# EVB-NORA-B2_SCHEM_0002_NORA_Module.net
KiCad netlist of a schematic drawn in Altium Designer
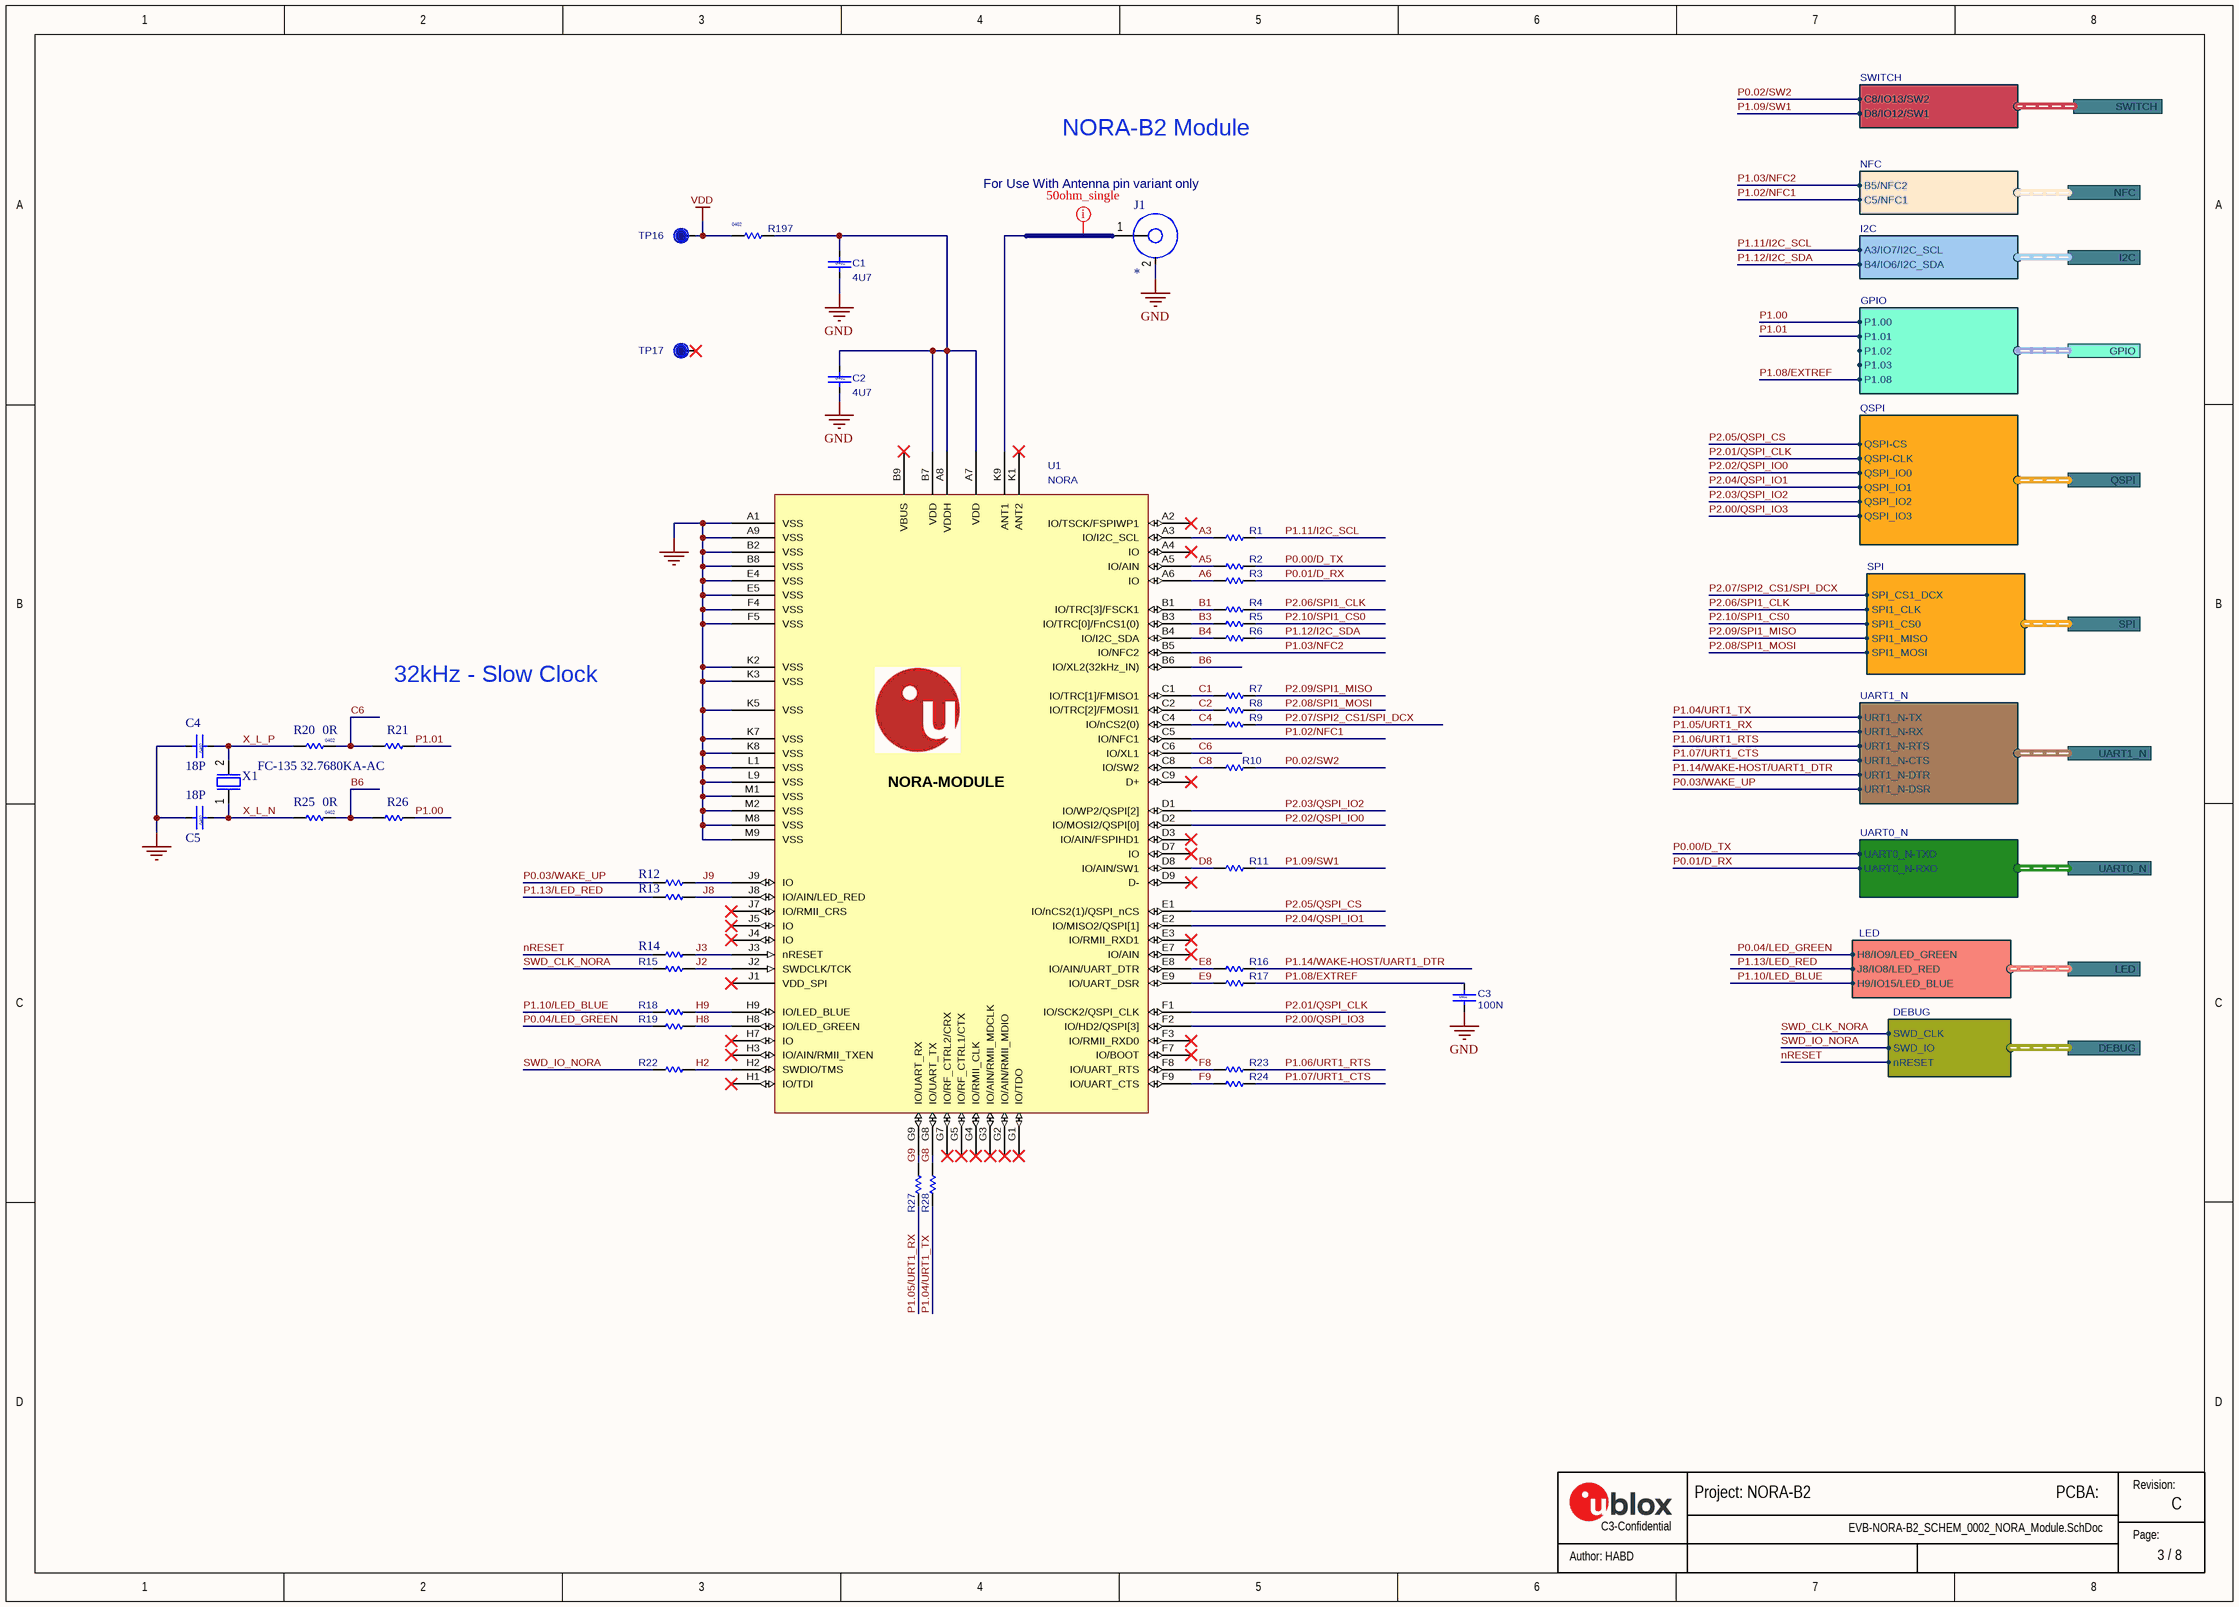
[diagram p0: EVB-NORA-B2_SCHEM_0002_NORA_Module.SchDoc]

(export (version "E")
  (design (tool "Eeschema 10.0.6"))
  (components
    (comp (ref "C1")
      (value "4U7")
      (footprint "Cap 0402 HD")
      (description "CAP CER X5R 0402 4U7 20% 10V")
      (fields
        (field (name "SIZE") "0402")
        (field (name "PART NUMBER") "UBXH01-0000243")
        (field (name "TOLERANCE") "20%")
        (field (name "EDITOR") "martin.pilik")
        (field (name "RELEASED BY") "fabrice.bret-dibat")
      )
      (libsource (lib "UBX_Parts_DB_Lib") (part "Cap Chip"))
    )
    (comp (ref "C2")
      (value "4U7")
      (footprint "Cap 0402 HD")
      (description "CAP CER X5R 0402 4U7 20% 10V")
      (fields
        (field (name "SIZE") "0402")
        (field (name "PART NUMBER") "UBXH01-0000243")
        (field (name "TOLERANCE") "20%")
        (field (name "EDITOR") "martin.pilik")
        (field (name "RELEASED BY") "fabrice.bret-dibat")
      )
      (libsource (lib "UBX_Parts_DB_Lib") (part "Cap Chip"))
    )
    (comp (ref "C3")
      (value "100N")
      (footprint "Cap 0402 HD")
      (description "CAP CER X5R 0402 100N 10% 10V")
      (fields
        (field (name "SIZE") "0402")
        (field (name "PART NUMBER") "UBXH01-2021002")
        (field (name "TOLERANCE") "10%")
        (field (name "EDITOR") "roland.rust")
        (field (name "RELEASED BY") "roland.rust")
      )
      (libsource (lib "UBX_Parts_DB_Lib") (part "Cap Chip"))
    )
    (comp (ref "C4")
      (value "18P")
      (footprint "Cap_0402_1100Lx600Wx600H_600x600Pad_350G_FLX")
      (description "CAP CER C0G 0402 18P 5% 25V")
      (fields
        (field (name "SIZE") "0402")
        (field (name "PART NUMBER") "UBXH01-0004017")
        (field (name "TOLERANCE") "5%")
        (field (name "EDITOR") "doris.zahnd")
        (field (name "RELEASED BY") "daniel.hurni")
      )
      (libsource (lib "UBX_Parts_DB_Lib") (part "Cap Chip"))
    )
    (comp (ref "C5")
      (value "18P")
      (footprint "Cap_0402_1100Lx600Wx600H_600x600Pad_350G_FLX")
      (description "CAP CER C0G 0402 18P 5% 25V")
      (fields
        (field (name "SIZE") "0402")
        (field (name "PART NUMBER") "UBXH01-0004017")
        (field (name "TOLERANCE") "5%")
        (field (name "EDITOR") "doris.zahnd")
        (field (name "RELEASED BY") "daniel.hurni")
      )
      (libsource (lib "UBX_Parts_DB_Lib") (part "Cap Chip"))
    )
    (comp (ref "J1")
      (value "130-00067")
      (footprint "U.FL_3Pin")
      (description "U.FL jack, SMA 50 ohm, 3 pin, SMT")
      (fields (field (name "MANUFACTURER P/N") "*") (field (name "VOLTAGE") "None"))
      (libsource (lib "Arena_Parts_DB_Lib") (part "CON_Coax_2Pin"))
    )
    (comp (ref "R1")
      (value "UBXH18-0003002")
      (footprint "RES 0402 HD")
      (description "RES THICK FILM CHIP 0402 0R 0 100mW")
      (fields
        (field (name "TOLERANCE") "0")
        (field (name "MANUFACTURER") "KOA")
        (field (name "EDITOR") "charlotte.biber")
        (field (name "RELEASED BY") "peter.mueller")
      )
      (libsource (lib "UBX_Parts_DB_Lib") (part "Res sm"))
    )
    (comp (ref "R2")
      (value "UBXH18-0003002")
      (footprint "RES 0402 HD")
      (description "RES THICK FILM CHIP 0402 0R 0 100mW")
      (fields
        (field (name "TOLERANCE") "0")
        (field (name "MANUFACTURER") "KOA")
        (field (name "EDITOR") "charlotte.biber")
        (field (name "RELEASED BY") "peter.mueller")
      )
      (libsource (lib "UBX_Parts_DB_Lib") (part "Res sm"))
    )
    (comp (ref "R3")
      (value "UBXH18-0003002")
      (footprint "RES 0402 HD")
      (description "RES THICK FILM CHIP 0402 0R 0 100mW")
      (fields
        (field (name "TOLERANCE") "0")
        (field (name "MANUFACTURER") "KOA")
        (field (name "EDITOR") "charlotte.biber")
        (field (name "RELEASED BY") "peter.mueller")
      )
      (libsource (lib "UBX_Parts_DB_Lib") (part "Res sm"))
    )
    (comp (ref "R4")
      (value "UBXH18-0003002")
      (footprint "RES 0402 HD")
      (description "RES THICK FILM CHIP 0402 0R 0 100mW")
      (fields
        (field (name "TOLERANCE") "0")
        (field (name "MANUFACTURER") "KOA")
        (field (name "EDITOR") "charlotte.biber")
        (field (name "RELEASED BY") "peter.mueller")
      )
      (libsource (lib "UBX_Parts_DB_Lib") (part "Res sm"))
    )
    (comp (ref "R5")
      (value "UBXH18-0003002")
      (footprint "RES 0402 HD")
      (description "RES THICK FILM CHIP 0402 0R 0 100mW")
      (fields
        (field (name "TOLERANCE") "0")
        (field (name "MANUFACTURER") "KOA")
        (field (name "EDITOR") "charlotte.biber")
        (field (name "RELEASED BY") "peter.mueller")
      )
      (libsource (lib "UBX_Parts_DB_Lib") (part "Res sm"))
    )
    (comp (ref "R6")
      (value "UBXH18-0003002")
      (footprint "RES 0402 HD")
      (description "RES THICK FILM CHIP 0402 0R 0 100mW")
      (fields
        (field (name "TOLERANCE") "0")
        (field (name "MANUFACTURER") "KOA")
        (field (name "EDITOR") "charlotte.biber")
        (field (name "RELEASED BY") "peter.mueller")
      )
      (libsource (lib "UBX_Parts_DB_Lib") (part "Res sm"))
    )
    (comp (ref "R7")
      (value "UBXH18-0003002")
      (footprint "RES 0402 HD")
      (description "RES THICK FILM CHIP 0402 0R 0 100mW")
      (fields
        (field (name "TOLERANCE") "0")
        (field (name "MANUFACTURER") "KOA")
        (field (name "EDITOR") "charlotte.biber")
        (field (name "RELEASED BY") "peter.mueller")
      )
      (libsource (lib "UBX_Parts_DB_Lib") (part "Res sm"))
    )
    (comp (ref "R8")
      (value "UBXH18-0003002")
      (footprint "RES 0402 HD")
      (description "RES THICK FILM CHIP 0402 0R 0 100mW")
      (fields
        (field (name "TOLERANCE") "0")
        (field (name "MANUFACTURER") "KOA")
        (field (name "EDITOR") "charlotte.biber")
        (field (name "RELEASED BY") "peter.mueller")
      )
      (libsource (lib "UBX_Parts_DB_Lib") (part "Res sm"))
    )
    (comp (ref "R9")
      (value "UBXH18-0003002")
      (footprint "RES 0402 HD")
      (description "RES THICK FILM CHIP 0402 0R 0 100mW")
      (fields
        (field (name "TOLERANCE") "0")
        (field (name "MANUFACTURER") "KOA")
        (field (name "EDITOR") "charlotte.biber")
        (field (name "RELEASED BY") "peter.mueller")
      )
      (libsource (lib "UBX_Parts_DB_Lib") (part "Res sm"))
    )
    (comp (ref "R10")
      (value "UBXH18-0003002")
      (footprint "RES 0402 HD")
      (description "RES THICK FILM CHIP 0402 0R 0 100mW")
      (fields
        (field (name "TOLERANCE") "0")
        (field (name "MANUFACTURER") "KOA")
        (field (name "EDITOR") "charlotte.biber")
        (field (name "RELEASED BY") "peter.mueller")
      )
      (libsource (lib "UBX_Parts_DB_Lib") (part "Res sm"))
    )
    (comp (ref "R11")
      (value "UBXH18-0003002")
      (footprint "RES 0402 HD")
      (description "RES THICK FILM CHIP 0402 0R 0 100mW")
      (fields
        (field (name "TOLERANCE") "0")
        (field (name "MANUFACTURER") "KOA")
        (field (name "EDITOR") "charlotte.biber")
        (field (name "RELEASED BY") "peter.mueller")
      )
      (libsource (lib "UBX_Parts_DB_Lib") (part "Res sm"))
    )
    (comp (ref "R12")
      (value "UBXH18-0003002")
      (footprint "RES_0402_1100Lx600Wx400H_500x600Pad_400G_FLX")
      (description "RES THICK FILM CHIP 0402 0R 0 100mW")
      (fields
        (field (name "TOLERANCE") "0")
        (field (name "MANUFACTURER") "KOA")
        (field (name "EDITOR") "charlotte.biber")
        (field (name "RELEASED BY") "peter.mueller")
      )
      (libsource (lib "UBX_Parts_DB_Lib") (part "Res sm"))
    )
    (comp (ref "R13")
      (value "UBXH18-0003002")
      (footprint "RES_0402_1100Lx600Wx400H_500x600Pad_400G_FLX")
      (description "RES THICK FILM CHIP 0402 0R 0 100mW")
      (fields
        (field (name "TOLERANCE") "0")
        (field (name "MANUFACTURER") "KOA")
        (field (name "EDITOR") "charlotte.biber")
        (field (name "RELEASED BY") "peter.mueller")
      )
      (libsource (lib "UBX_Parts_DB_Lib") (part "Res sm"))
    )
    (comp (ref "R14")
      (value "UBXH18-0003002")
      (footprint "RES_0402_1100Lx600Wx400H_500x600Pad_400G_FLX")
      (description "RES THICK FILM CHIP 0402 0R 0 100mW")
      (fields
        (field (name "TOLERANCE") "0")
        (field (name "MANUFACTURER") "KOA")
        (field (name "EDITOR") "charlotte.biber")
        (field (name "RELEASED BY") "peter.mueller")
      )
      (libsource (lib "UBX_Parts_DB_Lib") (part "Res sm"))
    )
    (comp (ref "R15")
      (value "UBXH18-0003002")
      (footprint "RES 0402 HD")
      (description "RES THICK FILM CHIP 0402 0R 0 100mW")
      (fields
        (field (name "TOLERANCE") "0")
        (field (name "MANUFACTURER") "KOA")
        (field (name "EDITOR") "charlotte.biber")
        (field (name "RELEASED BY") "peter.mueller")
      )
      (libsource (lib "UBX_Parts_DB_Lib") (part "Res sm"))
    )
    (comp (ref "R16")
      (value "UBXH18-0003002")
      (footprint "RES 0402 HD")
      (description "RES THICK FILM CHIP 0402 0R 0 100mW")
      (fields
        (field (name "TOLERANCE") "0")
        (field (name "MANUFACTURER") "KOA")
        (field (name "EDITOR") "charlotte.biber")
        (field (name "RELEASED BY") "peter.mueller")
      )
      (libsource (lib "UBX_Parts_DB_Lib") (part "Res sm"))
    )
    (comp (ref "R17")
      (value "UBXH18-0003002")
      (footprint "RES 0402 HD")
      (description "RES THICK FILM CHIP 0402 0R 0 100mW")
      (fields
        (field (name "TOLERANCE") "0")
        (field (name "MANUFACTURER") "KOA")
        (field (name "EDITOR") "charlotte.biber")
        (field (name "RELEASED BY") "peter.mueller")
      )
      (libsource (lib "UBX_Parts_DB_Lib") (part "Res sm"))
    )
    (comp (ref "R18")
      (value "UBXH18-0003002")
      (footprint "RES 0402 HD")
      (description "RES THICK FILM CHIP 0402 0R 0 100mW")
      (fields
        (field (name "TOLERANCE") "0")
        (field (name "MANUFACTURER") "KOA")
        (field (name "EDITOR") "charlotte.biber")
        (field (name "RELEASED BY") "peter.mueller")
      )
      (libsource (lib "UBX_Parts_DB_Lib") (part "Res sm"))
    )
    (comp (ref "R19")
      (value "UBXH18-0003002")
      (footprint "RES 0402 HD")
      (description "RES THICK FILM CHIP 0402 0R 0 100mW")
      (fields
        (field (name "TOLERANCE") "0")
        (field (name "MANUFACTURER") "KOA")
        (field (name "EDITOR") "charlotte.biber")
        (field (name "RELEASED BY") "peter.mueller")
      )
      (libsource (lib "UBX_Parts_DB_Lib") (part "Res sm"))
    )
    (comp (ref "R20")
      (value "0R")
      (footprint "RES 0402 HD")
      (description "RES THICK FILM CHIP 0402 0R 0 100mW")
      (fields
        (field (name "SIZE") "0402")
        (field (name "PART NUMBER") "UBXH18-0003002")
        (field (name "TOLERANCE") "0")
        (field (name "EDITOR") "charlotte.biber")
        (field (name "RELEASED BY") "peter.mueller")
      )
      (libsource (lib "UBX_Parts_DB_Lib") (part "Res sm"))
    )
    (comp (ref "R21")
      (value "UBXH18-0003002")
      (footprint "RES_0402_1100Lx600Wx400H_500x600Pad_400G_FLX")
      (description "RES THICK FILM CHIP 0402 0R 0 100mW")
      (fields
        (field (name "TOLERANCE") "0")
        (field (name "MANUFACTURER") "KOA")
        (field (name "EDITOR") "charlotte.biber")
        (field (name "RELEASED BY") "peter.mueller")
      )
      (libsource (lib "UBX_Parts_DB_Lib") (part "Res sm"))
    )
    (comp (ref "R22")
      (value "UBXH18-0003002")
      (footprint "RES 0402 HD")
      (description "RES THICK FILM CHIP 0402 0R 0 100mW")
      (fields
        (field (name "TOLERANCE") "0")
        (field (name "MANUFACTURER") "KOA")
        (field (name "EDITOR") "charlotte.biber")
        (field (name "RELEASED BY") "peter.mueller")
      )
      (libsource (lib "UBX_Parts_DB_Lib") (part "Res sm"))
    )
    (comp (ref "R23")
      (value "UBXH18-0003002")
      (footprint "RES 0402 HD")
      (description "RES THICK FILM CHIP 0402 0R 0 100mW")
      (fields
        (field (name "TOLERANCE") "0")
        (field (name "MANUFACTURER") "KOA")
        (field (name "EDITOR") "charlotte.biber")
        (field (name "RELEASED BY") "peter.mueller")
      )
      (libsource (lib "UBX_Parts_DB_Lib") (part "Res sm"))
    )
    (comp (ref "R24")
      (value "UBXH18-0003002")
      (footprint "RES 0402 HD")
      (description "RES THICK FILM CHIP 0402 0R 0 100mW")
      (fields
        (field (name "TOLERANCE") "0")
        (field (name "MANUFACTURER") "KOA")
        (field (name "EDITOR") "charlotte.biber")
        (field (name "RELEASED BY") "peter.mueller")
      )
      (libsource (lib "UBX_Parts_DB_Lib") (part "Res sm"))
    )
    (comp (ref "R25")
      (value "0R")
      (footprint "RES 0402 HD")
      (description "RES THICK FILM CHIP 0402 0R 0 100mW")
      (fields
        (field (name "SIZE") "0402")
        (field (name "PART NUMBER") "UBXH18-0003002")
        (field (name "TOLERANCE") "0")
        (field (name "EDITOR") "charlotte.biber")
        (field (name "RELEASED BY") "peter.mueller")
      )
      (libsource (lib "UBX_Parts_DB_Lib") (part "Res sm"))
    )
    (comp (ref "R26")
      (value "UBXH18-0003002")
      (footprint "RES_0402_1100Lx600Wx400H_500x600Pad_400G_FLX")
      (description "RES THICK FILM CHIP 0402 0R 0 100mW")
      (fields
        (field (name "TOLERANCE") "0")
        (field (name "MANUFACTURER") "KOA")
        (field (name "EDITOR") "charlotte.biber")
        (field (name "RELEASED BY") "peter.mueller")
      )
      (libsource (lib "UBX_Parts_DB_Lib") (part "Res sm"))
    )
    (comp (ref "R27")
      (value "UBXH18-0003002")
      (footprint "RES 0402 HD")
      (description "RES THICK FILM CHIP 0402 0R 0 100mW")
      (fields
        (field (name "TOLERANCE") "0")
        (field (name "MANUFACTURER") "KOA")
        (field (name "EDITOR") "charlotte.biber")
        (field (name "RELEASED BY") "peter.mueller")
      )
      (libsource (lib "UBX_Parts_DB_Lib") (part "Res sm"))
    )
    (comp (ref "R28")
      (value "UBXH18-0003002")
      (footprint "RES 0402 HD")
      (description "RES THICK FILM CHIP 0402 0R 0 100mW")
      (fields
        (field (name "TOLERANCE") "0")
        (field (name "MANUFACTURER") "KOA")
        (field (name "EDITOR") "charlotte.biber")
        (field (name "RELEASED BY") "peter.mueller")
      )
      (libsource (lib "UBX_Parts_DB_Lib") (part "Res sm"))
    )
    (comp (ref "R197")
      (value "UBXH18-0003002")
      (footprint "RES 0402 HD")
      (description "RES THICK FILM CHIP 0402 0R 0 100mW")
      (fields
        (field (name "SIZE") "0402")
        (field (name "TOLERANCE") "0")
        (field (name "MANUFACTURER") "KOA")
        (field (name "EDITOR") "charlotte.biber")
        (field (name "RELEASED BY") "peter.mueller")
      )
      (libsource (lib "UBX_Parts_DB_Lib") (part "Res sm"))
    )
    (comp (ref "TP16")
      (value "TP10R")
      (footprint "TP10R")
      (description "Testpoint, Round 1.0mm Dia")
      (fields (field (name "ADDED BY") "Jeremy D") (field (name "CHECKED BY") "Paul B"))
      (libsource (lib "LEGACY_Rigado_AltiumLib") (part "TP_R"))
    )
    (comp (ref "TP17")
      (value "TP10R")
      (footprint "TP10R")
      (description "Testpoint, Round 1.0mm Dia")
      (fields (field (name "ADDED BY") "Jeremy D") (field (name "CHECKED BY") "Paul B"))
      (libsource (lib "LEGACY_Rigado_AltiumLib") (part "TP_R"))
    )
    (comp (ref "U1")
      (value "NORA")
      (footprint "NORA:NORA_LGA82R_1430X1040X180_ANT")
      (description "u-blox NORA module generic symbol for use within module designs - alternate version")
      (fields (field (name "MANUFACTURER") "u-blox"))
      (libsource (lib "NORA") (part "NORA-MODULE_ALT"))
    )
    (comp (ref "X1")
      (value "UBXH21-0008104")
      (footprint "XTAL_3215")
      (description "CRYSTAL CL=9PF EPSON FC-135 NI/SN TERMINATION 32.768KHz")
      (fields (field (name "MANUFACTURER P/N") "FC-135 32.7680KA-AC") (field (name "OWNER") "Andreas Thiel"))
      (libsource (lib "UBX_Arena") (part "XTAL_2Pin"))
    )
  )
  (nets
    (net (code "11") (name "/A3") (class "Default")
      (node (ref "R1") (pin "2") (pinfunction "2_2") (pintype "passive"))
      (node (ref "U1") (pin "A3") (pinfunction "IO/I2C_SCL_A3") (pintype "bidirectional"))
    )
    (net (code "12") (name "/A5") (class "Default")
      (node (ref "R2") (pin "2") (pinfunction "2_2") (pintype "passive"))
      (node (ref "U1") (pin "A5") (pinfunction "IO/AIN_A5") (pintype "bidirectional"))
    )
    (net (code "13") (name "/A6") (class "Default")
      (node (ref "R3") (pin "2") (pinfunction "2_2") (pintype "passive"))
      (node (ref "U1") (pin "A6") (pinfunction "IO_A6") (pintype "bidirectional"))
    )
    (net (code "14") (name "/B1") (class "Default")
      (node (ref "R4") (pin "2") (pinfunction "2_2") (pintype "passive"))
      (node (ref "U1") (pin "B1") (pinfunction "IO/TRC[3]/FSCK1_B1") (pintype "bidirectional"))
    )
    (net (code "15") (name "/B3") (class "Default")
      (node (ref "R5") (pin "2") (pinfunction "2_2") (pintype "passive"))
      (node (ref "U1") (pin "B3") (pinfunction "IO/TRC[0]/FnCS1(0)_B3") (pintype "bidirectional"))
    )
    (net (code "16") (name "/B4") (class "Default")
      (node (ref "R6") (pin "2") (pinfunction "2_2") (pintype "passive"))
      (node (ref "U1") (pin "B4") (pinfunction "IO/I2C_SDA_B4") (pintype "bidirectional"))
    )
    (net (code "17") (name "/B6") (class "Default")
      (node (ref "R25") (pin "2") (pinfunction "2_2") (pintype "passive"))
      (node (ref "R26") (pin "2") (pinfunction "2_2") (pintype "passive"))
      (node (ref "U1") (pin "B6") (pinfunction "IO/XL2(32kHz_IN)_B6") (pintype "bidirectional"))
    )
    (net (code "18") (name "/C1") (class "Default")
      (node (ref "R7") (pin "2") (pinfunction "2_2") (pintype "passive"))
      (node (ref "U1") (pin "C1") (pinfunction "IO/TRC[1]/FMISO1_C1") (pintype "bidirectional"))
    )
    (net (code "19") (name "/C2") (class "Default")
      (node (ref "R8") (pin "2") (pinfunction "2_2") (pintype "passive"))
      (node (ref "U1") (pin "C2") (pinfunction "IO/TRC[2]/FMOSI1_C2") (pintype "bidirectional"))
    )
    (net (code "20") (name "/C4") (class "Default")
      (node (ref "R9") (pin "2") (pinfunction "2_2") (pintype "passive"))
      (node (ref "U1") (pin "C4") (pinfunction "IO/nCS2(0)_C4") (pintype "bidirectional"))
    )
    (net (code "21") (name "/C6") (class "Default")
      (node (ref "R20") (pin "2") (pinfunction "2_2") (pintype "passive"))
      (node (ref "R21") (pin "2") (pinfunction "2_2") (pintype "passive"))
      (node (ref "U1") (pin "C6") (pinfunction "IO/XL1_C6") (pintype "bidirectional"))
    )
    (net (code "22") (name "/C8") (class "Default")
      (node (ref "R10") (pin "2") (pinfunction "2_2") (pintype "passive"))
      (node (ref "U1") (pin "C8") (pinfunction "IO/SW2_C8") (pintype "bidirectional"))
    )
    (net (code "23") (name "/D8") (class "Default")
      (node (ref "R11") (pin "2") (pinfunction "2_2") (pintype "passive"))
      (node (ref "U1") (pin "D8") (pinfunction "IO/AIN/SW1_D8") (pintype "bidirectional"))
    )
    (net (code "24") (name "/E8") (class "Default")
      (node (ref "R16") (pin "2") (pinfunction "2_2") (pintype "passive"))
      (node (ref "U1") (pin "E8") (pinfunction "IO/AIN/UART_DTR_E8") (pintype "bidirectional"))
    )
    (net (code "25") (name "/E9") (class "Default")
      (node (ref "R17") (pin "2") (pinfunction "2_2") (pintype "passive"))
      (node (ref "U1") (pin "E9") (pinfunction "IO/UART_DSR_E9") (pintype "bidirectional"))
    )
    (net (code "26") (name "/F8") (class "Default")
      (node (ref "R23") (pin "2") (pinfunction "2_2") (pintype "passive"))
      (node (ref "U1") (pin "F8") (pinfunction "IO/UART_RTS_F8") (pintype "bidirectional"))
    )
    (net (code "27") (name "/F9") (class "Default")
      (node (ref "R24") (pin "2") (pinfunction "2_2") (pintype "passive"))
      (node (ref "U1") (pin "F9") (pinfunction "IO/UART_CTS_F9") (pintype "bidirectional"))
    )
    (net (code "28") (name "/G8") (class "Default")
      (node (ref "R28") (pin "1") (pinfunction "1_1") (pintype "passive"))
      (node (ref "U1") (pin "G8") (pinfunction "IO/UART_TX_G8") (pintype "bidirectional"))
    )
    (net (code "29") (name "/G9") (class "Default")
      (node (ref "R27") (pin "1") (pinfunction "1_1") (pintype "passive"))
      (node (ref "U1") (pin "G9") (pinfunction "IO/UART_RX_G9") (pintype "bidirectional"))
    )
    (net (code "30") (name "/H2") (class "Default")
      (node (ref "R22") (pin "1") (pinfunction "1_1") (pintype "passive"))
      (node (ref "U1") (pin "H2") (pinfunction "SWDIO/TMS_H2") (pintype "bidirectional"))
    )
    (net (code "31") (name "/H8") (class "Default")
      (node (ref "R19") (pin "1") (pinfunction "1_1") (pintype "passive"))
      (node (ref "U1") (pin "H8") (pinfunction "IO/LED_GREEN_H8") (pintype "bidirectional"))
    )
    (net (code "32") (name "/H9") (class "Default")
      (node (ref "R18") (pin "1") (pinfunction "1_1") (pintype "passive"))
      (node (ref "U1") (pin "H9") (pinfunction "IO/LED_BLUE_H9") (pintype "bidirectional"))
    )
    (net (code "33") (name "/J2") (class "Default")
      (node (ref "R15") (pin "1") (pinfunction "1_1") (pintype "passive"))
      (node (ref "U1") (pin "J2") (pinfunction "SWDCLK/TCK_J2") (pintype "input"))
    )
    (net (code "34") (name "/J3") (class "Default")
      (node (ref "R14") (pin "1") (pinfunction "1_1") (pintype "passive"))
      (node (ref "U1") (pin "J3") (pinfunction "nRESET_J3") (pintype "input"))
    )
    (net (code "35") (name "/J8") (class "Default")
      (node (ref "R13") (pin "1") (pinfunction "1_1") (pintype "passive"))
      (node (ref "U1") (pin "J8") (pinfunction "IO/AIN/LED_RED_J8") (pintype "bidirectional"))
    )
    (net (code "36") (name "/J9") (class "Default")
      (node (ref "R12") (pin "1") (pinfunction "1_1") (pintype "passive"))
      (node (ref "U1") (pin "J9") (pinfunction "IO_J9") (pintype "bidirectional"))
    )
    (net (code "37") (name "/P0.00{slash}D_TX") (class "Default")
      (node (ref "R2") (pin "1") (pinfunction "1_1") (pintype "passive"))
    )
    (net (code "38") (name "/P0.01{slash}D_RX") (class "Default")
      (node (ref "R3") (pin "1") (pinfunction "1_1") (pintype "passive"))
    )
    (net (code "39") (name "/P0.02{slash}SW2") (class "Default")
      (node (ref "R10") (pin "1") (pinfunction "1_1") (pintype "passive"))
    )
    (net (code "40") (name "/P0.03{slash}WAKE_UP") (class "Default")
      (node (ref "R12") (pin "2") (pinfunction "2_2") (pintype "passive"))
    )
    (net (code "41") (name "/P0.04{slash}LED_GREEN") (class "Default")
      (node (ref "R19") (pin "2") (pinfunction "2_2") (pintype "passive"))
    )
    (net (code "42") (name "/P1.00") (class "Default")
      (node (ref "R26") (pin "1") (pinfunction "1_1") (pintype "passive"))
    )
    (net (code "43") (name "/P1.01") (class "Default")
      (node (ref "R21") (pin "1") (pinfunction "1_1") (pintype "passive"))
    )
    (net (code "44") (name "/P1.02{slash}NFC1") (class "Default")
      (node (ref "U1") (pin "C5") (pinfunction "IO/NFC1_C5") (pintype "bidirectional"))
    )
    (net (code "45") (name "/P1.03{slash}NFC2") (class "Default")
      (node (ref "U1") (pin "B5") (pinfunction "IO/NFC2_B5") (pintype "bidirectional"))
    )
    (net (code "46") (name "/P1.04{slash}URT1_TX") (class "Default")
      (node (ref "R28") (pin "2") (pinfunction "2_2") (pintype "passive"))
    )
    (net (code "47") (name "/P1.05{slash}URT1_RX") (class "Default")
      (node (ref "R27") (pin "2") (pinfunction "2_2") (pintype "passive"))
    )
    (net (code "48") (name "/P1.06{slash}URT1_RTS") (class "Default")
      (node (ref "R23") (pin "1") (pinfunction "1_1") (pintype "passive"))
    )
    (net (code "49") (name "/P1.07{slash}URT1_CTS") (class "Default")
      (node (ref "R24") (pin "1") (pinfunction "1_1") (pintype "passive"))
    )
    (net (code "50") (name "/P1.08{slash}EXTREF") (class "Default")
      (node (ref "C3") (pin "2") (pinfunction "2_2") (pintype "passive"))
      (node (ref "R17") (pin "1") (pinfunction "1_1") (pintype "passive"))
    )
    (net (code "51") (name "/P1.09{slash}SW1") (class "Default")
      (node (ref "R11") (pin "1") (pinfunction "1_1") (pintype "passive"))
    )
    (net (code "52") (name "/P1.10{slash}LED_BLUE") (class "Default")
      (node (ref "R18") (pin "2") (pinfunction "2_2") (pintype "passive"))
    )
    (net (code "53") (name "/P1.11{slash}I2C_SCL") (class "Default")
      (node (ref "R1") (pin "1") (pinfunction "1_1") (pintype "passive"))
    )
    (net (code "54") (name "/P1.12{slash}I2C_SDA") (class "Default")
      (node (ref "R6") (pin "1") (pinfunction "1_1") (pintype "passive"))
    )
    (net (code "55") (name "/P1.13{slash}LED_RED") (class "Default")
      (node (ref "R13") (pin "2") (pinfunction "2_2") (pintype "passive"))
    )
    (net (code "56") (name "/P1.14{slash}WAKE-HOST{slash}UART1_DTR") (class "Default")
      (node (ref "R16") (pin "1") (pinfunction "1_1") (pintype "passive"))
    )
    (net (code "57") (name "/P2.00{slash}QSPI_IO3") (class "Default")
      (node (ref "U1") (pin "F2") (pinfunction "IO/HD2/QSPI[3]_F2") (pintype "bidirectional"))
    )
    (net (code "58") (name "/P2.01{slash}QSPI_CLK") (class "Default")
      (node (ref "U1") (pin "F1") (pinfunction "IO/SCK2/QSPI_CLK_F1") (pintype "bidirectional"))
    )
    (net (code "59") (name "/P2.02{slash}QSPI_IO0") (class "Default")
      (node (ref "U1") (pin "D2") (pinfunction "IO/MOSI2/QSPI[0]_D2") (pintype "bidirectional"))
    )
    (net (code "60") (name "/P2.03{slash}QSPI_IO2") (class "Default")
      (node (ref "U1") (pin "D1") (pinfunction "IO/WP2/QSPI[2]_D1") (pintype "bidirectional"))
    )
    (net (code "61") (name "/P2.04{slash}QSPI_IO1") (class "Default")
      (node (ref "U1") (pin "E2") (pinfunction "IO/MISO2/QSPI[1]_E2") (pintype "bidirectional"))
    )
    (net (code "62") (name "/P2.05{slash}QSPI_CS") (class "Default")
      (node (ref "U1") (pin "E1") (pinfunction "IO/nCS2(1)/QSPI_nCS_E1") (pintype "bidirectional"))
    )
    (net (code "63") (name "/P2.06{slash}SPI1_CLK") (class "Default")
      (node (ref "R4") (pin "1") (pinfunction "1_1") (pintype "passive"))
    )
    (net (code "64") (name "/P2.07{slash}SPI2_CS1{slash}SPI_DCX") (class "Default")
      (node (ref "R9") (pin "1") (pinfunction "1_1") (pintype "passive"))
    )
    (net (code "65") (name "/P2.08{slash}SPI1_MOSI") (class "Default")
      (node (ref "R8") (pin "1") (pinfunction "1_1") (pintype "passive"))
    )
    (net (code "66") (name "/P2.09{slash}SPI1_MISO") (class "Default")
      (node (ref "R7") (pin "1") (pinfunction "1_1") (pintype "passive"))
    )
    (net (code "67") (name "/P2.10{slash}SPI1_CS0") (class "Default")
      (node (ref "R5") (pin "1") (pinfunction "1_1") (pintype "passive"))
    )
    (net (code "68") (name "/SWD_CLK_NORA") (class "Default")
      (node (ref "R15") (pin "2") (pinfunction "2_2") (pintype "passive"))
    )
    (net (code "69") (name "/SWD_IO_NORA") (class "Default")
      (node (ref "R22") (pin "2") (pinfunction "2_2") (pintype "passive"))
    )
    (net (code "70") (name "/X_L_N") (class "Default")
      (node (ref "C5") (pin "1") (pinfunction "1_1") (pintype "passive"))
      (node (ref "R25") (pin "1") (pinfunction "1_1") (pintype "passive"))
      (node (ref "X1") (pin "1") (pintype "passive"))
    )
    (net (code "71") (name "/X_L_P") (class "Default")
      (node (ref "C4") (pin "1") (pinfunction "1_1") (pintype "passive"))
      (node (ref "R20") (pin "1") (pinfunction "1_1") (pintype "passive"))
      (node (ref "X1") (pin "2") (pintype "passive"))
    )
    (net (code "72") (name "/nRESET") (class "Default")
      (node (ref "R14") (pin "2") (pinfunction "2_2") (pintype "passive"))
    )
    (net (code "83") (name "GND") (class "Default")
      (node (ref "C1") (pin "2") (pinfunction "2_2") (pintype "passive"))
      (node (ref "C2") (pin "2") (pinfunction "2_2") (pintype "passive"))
      (node (ref "C3") (pin "1") (pinfunction "1_1") (pintype "passive"))
      (node (ref "C4") (pin "2") (pinfunction "2_2") (pintype "passive"))
      (node (ref "C5") (pin "2") (pinfunction "2_2") (pintype "passive"))
      (node (ref "J1") (pin "2") (pinfunction "2_2") (pintype "power_in"))
      (node (ref "U1") (pin "A1") (pinfunction "VSS_A1") (pintype "power_in"))
      (node (ref "U1") (pin "A9") (pinfunction "VSS_A9") (pintype "power_in"))
      (node (ref "U1") (pin "B2") (pinfunction "VSS_B2") (pintype "power_in"))
      (node (ref "U1") (pin "B8") (pinfunction "VSS_B8") (pintype "power_in"))
      (node (ref "U1") (pin "E4") (pinfunction "VSS_E4") (pintype "power_in"))
      (node (ref "U1") (pin "E5") (pinfunction "VSS_E5") (pintype "power_in"))
      (node (ref "U1") (pin "F4") (pinfunction "VSS_F4") (pintype "power_in"))
      (node (ref "U1") (pin "F5") (pinfunction "VSS_F5") (pintype "power_in"))
      (node (ref "U1") (pin "K2") (pinfunction "VSS_K2") (pintype "power_in"))
      (node (ref "U1") (pin "K3") (pinfunction "VSS_K3") (pintype "power_in"))
      (node (ref "U1") (pin "K5") (pinfunction "VSS_K5") (pintype "power_in"))
      (node (ref "U1") (pin "K7") (pinfunction "VSS_K7") (pintype "power_in"))
      (node (ref "U1") (pin "K8") (pinfunction "VSS_K8") (pintype "power_in"))
      (node (ref "U1") (pin "L1") (pinfunction "VSS_L1") (pintype "power_in"))
      (node (ref "U1") (pin "L9") (pinfunction "VSS_L9") (pintype "power_in"))
      (node (ref "U1") (pin "M1") (pinfunction "VSS_M1") (pintype "power_in"))
      (node (ref "U1") (pin "M2") (pinfunction "VSS_M2") (pintype "power_in"))
      (node (ref "U1") (pin "M8") (pinfunction "VSS_M8") (pintype "power_in"))
      (node (ref "U1") (pin "M9") (pinfunction "VSS_M9") (pintype "power_in"))
    )
    (net (code "84") (name "Net-(J1-ANT)") (class "Default")
      (node (ref "J1") (pin "1") (pinfunction "ANT_1") (pintype "passive"))
      (node (ref "U1") (pin "K9") (pinfunction "ANT1_K9") (pintype "passive"))
    )
    (net (code "85") (name "Net-(U1-VDDH)") (class "Default")
      (node (ref "C1") (pin "1") (pinfunction "1_1") (pintype "passive"))
      (node (ref "C2") (pin "1") (pinfunction "1_1") (pintype "passive"))
      (node (ref "R197") (pin "1") (pinfunction "1_1") (pintype "passive"))
      (node (ref "U1") (pin "A7") (pinfunction "VDD_A7") (pintype "power_in"))
      (node (ref "U1") (pin "A8") (pinfunction "VDDH_A8") (pintype "power_in"))
      (node (ref "U1") (pin "B7") (pinfunction "VDD_B7") (pintype "power_in"))
    )
    (net (code "86") (name "VDD") (class "Default")
      (node (ref "R197") (pin "2") (pinfunction "2_2") (pintype "passive"))
      (node (ref "TP16") (pin "1") (pintype "passive"))
    )
    (net (code "87") (name "unconnected-(TP17-Pad1)") (class "Default")
      (node (ref "TP17") (pin "1") (pintype "passive+no_connect"))
    )
    (net (code "88") (name "unconnected-(U1-ANT2-PadK1)") (class "Default")
      (node (ref "U1") (pin "K1") (pinfunction "ANT2_K1") (pintype "passive+no_connect"))
    )
    (net (code "89") (name "unconnected-(U1-D+-PadC9)") (class "Default")
      (node (ref "U1") (pin "C9") (pinfunction "D+_C9") (pintype "bidirectional+no_connect"))
    )
    (net (code "90") (name "unconnected-(U1-D--PadD9)") (class "Default")
      (node (ref "U1") (pin "D9") (pinfunction "D-_D9") (pintype "bidirectional+no_connect"))
    )
    (net (code "91") (name "unconnected-(U1-IO-PadA4)") (class "Default")
      (node (ref "U1") (pin "A4") (pinfunction "IO_A4") (pintype "bidirectional+no_connect"))
    )
    (net (code "92") (name "unconnected-(U1-IO-PadD7)") (class "Default")
      (node (ref "U1") (pin "D7") (pinfunction "IO_D7") (pintype "bidirectional+no_connect"))
    )
    (net (code "93") (name "unconnected-(U1-IO-PadH7)") (class "Default")
      (node (ref "U1") (pin "H7") (pinfunction "IO_H7") (pintype "bidirectional+no_connect"))
    )
    (net (code "94") (name "unconnected-(U1-IO-PadJ4)") (class "Default")
      (node (ref "U1") (pin "J4") (pinfunction "IO_J4") (pintype "bidirectional+no_connect"))
    )
    (net (code "95") (name "unconnected-(U1-IO-PadJ5)") (class "Default")
      (node (ref "U1") (pin "J5") (pinfunction "IO_J5") (pintype "bidirectional+no_connect"))
    )
    (net (code "96") (name "unconnected-(U1-IO{slash}AIN-PadE7)") (class "Default")
      (node (ref "U1") (pin "E7") (pinfunction "IO/AIN_E7") (pintype "bidirectional+no_connect"))
    )
    (net (code "97") (name "unconnected-(U1-IO{slash}AIN{slash}FSPIHD1-PadD3)") (class "Default")
      (node (ref "U1") (pin "D3") (pinfunction "IO/AIN/FSPIHD1_D3") (pintype "bidirectional+no_connect"))
    )
    (net (code "98") (name "unconnected-(U1-IO{slash}AIN{slash}RMII_MDCLK-PadG3)") (class "Default")
      (node (ref "U1") (pin "G3") (pinfunction "IO/AIN/RMII_MDCLK_G3") (pintype "bidirectional+no_connect"))
    )
    (net (code "99") (name "unconnected-(U1-IO{slash}AIN{slash}RMII_MDIO-PadG2)") (class "Default")
      (node (ref "U1") (pin "G2") (pinfunction "IO/AIN/RMII_MDIO_G2") (pintype "bidirectional+no_connect"))
    )
    (net (code "100") (name "unconnected-(U1-IO{slash}AIN{slash}RMII_TXEN-PadH3)") (class "Default")
      (node (ref "U1") (pin "H3") (pinfunction "IO/AIN/RMII_TXEN_H3") (pintype "bidirectional+no_connect"))
    )
    (net (code "101") (name "unconnected-(U1-IO{slash}BOOT-PadF7)") (class "Default")
      (node (ref "U1") (pin "F7") (pinfunction "IO/BOOT_F7") (pintype "bidirectional+no_connect"))
    )
    (net (code "102") (name "unconnected-(U1-IO{slash}RF_CTRL1{slash}CTX-PadG5)") (class "Default")
      (node (ref "U1") (pin "G5") (pinfunction "IO/RF_CTRL1/CTX_G5") (pintype "bidirectional+no_connect"))
    )
    (net (code "103") (name "unconnected-(U1-IO{slash}RF_CTRL2{slash}CRX-PadG7)") (class "Default")
      (node (ref "U1") (pin "G7") (pinfunction "IO/RF_CTRL2/CRX_G7") (pintype "bidirectional+no_connect"))
    )
    (net (code "104") (name "unconnected-(U1-IO{slash}RMII_CLK-PadG4)") (class "Default")
      (node (ref "U1") (pin "G4") (pinfunction "IO/RMII_CLK_G4") (pintype "bidirectional+no_connect"))
    )
    (net (code "105") (name "unconnected-(U1-IO{slash}RMII_CRS-PadJ7)") (class "Default")
      (node (ref "U1") (pin "J7") (pinfunction "IO/RMII_CRS_J7") (pintype "bidirectional+no_connect"))
    )
    (net (code "106") (name "unconnected-(U1-IO{slash}RMII_RXD0-PadF3)") (class "Default")
      (node (ref "U1") (pin "F3") (pinfunction "IO/RMII_RXD0_F3") (pintype "bidirectional+no_connect"))
    )
    (net (code "107") (name "unconnected-(U1-IO{slash}RMII_RXD1-PadE3)") (class "Default")
      (node (ref "U1") (pin "E3") (pinfunction "IO/RMII_RXD1_E3") (pintype "bidirectional+no_connect"))
    )
    (net (code "108") (name "unconnected-(U1-IO{slash}TDI-PadH1)") (class "Default")
      (node (ref "U1") (pin "H1") (pinfunction "IO/TDI_H1") (pintype "bidirectional+no_connect"))
    )
    (net (code "109") (name "unconnected-(U1-IO{slash}TDO-PadG1)") (class "Default")
      (node (ref "U1") (pin "G1") (pinfunction "IO/TDO_G1") (pintype "bidirectional+no_connect"))
    )
    (net (code "110") (name "unconnected-(U1-IO{slash}TSCK{slash}FSPIWP1-PadA2)") (class "Default")
      (node (ref "U1") (pin "A2") (pinfunction "IO/TSCK/FSPIWP1_A2") (pintype "bidirectional+no_connect"))
    )
    (net (code "111") (name "unconnected-(U1-VBUS-PadB9)") (class "Default")
      (node (ref "U1") (pin "B9") (pinfunction "VBUS_B9") (pintype "power_in+no_connect"))
    )
    (net (code "112") (name "unconnected-(U1-VDD_SPI-PadJ1)") (class "Default")
      (node (ref "U1") (pin "J1") (pinfunction "VDD_SPI_J1") (pintype "passive+no_connect"))
    )
  )
)
